# main.net
KiCad netlist of a schematic drawn in EAGLE
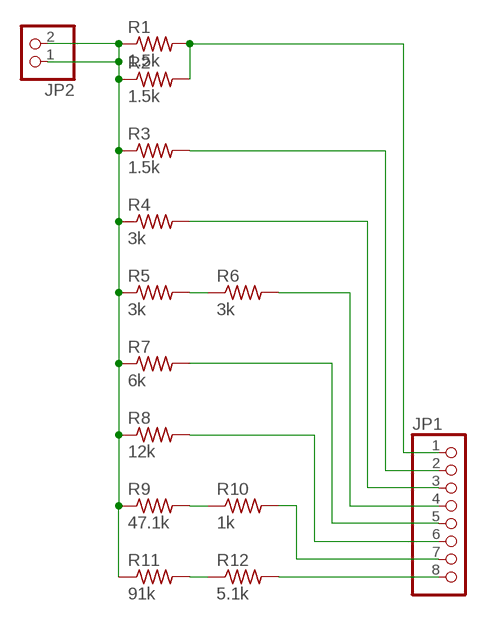
[diagram p0: schematic, sheet 1]

(export (version "E")
  (design (tool "Eeschema 10.0.6"))
  (components
    (comp (ref "JP1")
      (value "PINHD-1X8")
      (footprint "eagle-import:1X08")
      (libsource (lib "eagle-import") (part "PINHD-1X8"))
    )
    (comp (ref "JP2")
      (value "PINHD-1X2")
      (footprint "eagle-import:1X02")
      (libsource (lib "eagle-import") (part "PINHD-1X2"))
    )
    (comp (ref "R1")
      (value "1.5k")
      (footprint "eagle-import:0309_10")
      (libsource (lib "eagle-import") (part "R-US_0309/10"))
    )
    (comp (ref "R2")
      (value "1.5k")
      (footprint "eagle-import:0309_10")
      (libsource (lib "eagle-import") (part "R-US_0309/10"))
    )
    (comp (ref "R3")
      (value "1.5k")
      (footprint "eagle-import:0309_10")
      (libsource (lib "eagle-import") (part "R-US_0309/10"))
    )
    (comp (ref "R4")
      (value "3k")
      (footprint "eagle-import:0309_10")
      (libsource (lib "eagle-import") (part "R-US_0309/10"))
    )
    (comp (ref "R5")
      (value "3k")
      (footprint "eagle-import:0309_10")
      (libsource (lib "eagle-import") (part "R-US_0309/10"))
    )
    (comp (ref "R6")
      (value "3k")
      (footprint "eagle-import:0309_10")
      (libsource (lib "eagle-import") (part "R-US_0309/10"))
    )
    (comp (ref "R7")
      (value "6k")
      (footprint "eagle-import:0309_10")
      (libsource (lib "eagle-import") (part "R-US_0309/10"))
    )
    (comp (ref "R8")
      (value "12k")
      (footprint "eagle-import:0309_10")
      (libsource (lib "eagle-import") (part "R-US_0309/10"))
    )
    (comp (ref "R9")
      (value "47.1k")
      (footprint "eagle-import:0309_10")
      (libsource (lib "eagle-import") (part "R-US_0309/10"))
    )
    (comp (ref "R10")
      (value "1k")
      (footprint "eagle-import:0309_10")
      (libsource (lib "eagle-import") (part "R-US_0309/10"))
    )
    (comp (ref "R11")
      (value "91k")
      (footprint "eagle-import:0309_10")
      (libsource (lib "eagle-import") (part "R-US_0309/10"))
    )
    (comp (ref "R12")
      (value "5.1k")
      (footprint "eagle-import:0309_10")
      (libsource (lib "eagle-import") (part "R-US_0309/10"))
    )
  )
  (nets
    (net (code "1") (name "Net-(JP1-Pad1)") (class "Default")
      (node (ref "JP1") (pin "1") (pinfunction "1_1") (pintype "passive"))
      (node (ref "R1") (pin "2") (pinfunction "2_2") (pintype "passive"))
      (node (ref "R2") (pin "2") (pinfunction "2_2") (pintype "passive"))
    )
    (net (code "2") (name "Net-(JP1-Pad2)") (class "Default")
      (node (ref "JP1") (pin "2") (pinfunction "2_2") (pintype "passive"))
      (node (ref "R3") (pin "2") (pinfunction "2_2") (pintype "passive"))
    )
    (net (code "3") (name "Net-(JP1-Pad3)") (class "Default")
      (node (ref "JP1") (pin "3") (pinfunction "3_3") (pintype "passive"))
      (node (ref "R4") (pin "2") (pinfunction "2_2") (pintype "passive"))
    )
    (net (code "4") (name "Net-(JP1-Pad4)") (class "Default")
      (node (ref "JP1") (pin "4") (pinfunction "4_4") (pintype "passive"))
      (node (ref "R6") (pin "2") (pinfunction "2_2") (pintype "passive"))
    )
    (net (code "5") (name "Net-(JP1-Pad5)") (class "Default")
      (node (ref "JP1") (pin "5") (pinfunction "5_5") (pintype "passive"))
      (node (ref "R7") (pin "2") (pinfunction "2_2") (pintype "passive"))
    )
    (net (code "6") (name "Net-(JP1-Pad6)") (class "Default")
      (node (ref "JP1") (pin "6") (pinfunction "6_6") (pintype "passive"))
      (node (ref "R8") (pin "2") (pinfunction "2_2") (pintype "passive"))
    )
    (net (code "7") (name "Net-(JP1-Pad7)") (class "Default")
      (node (ref "JP1") (pin "7") (pinfunction "7_7") (pintype "passive"))
      (node (ref "R10") (pin "2") (pinfunction "2_2") (pintype "passive"))
    )
    (net (code "8") (name "Net-(JP1-Pad8)") (class "Default")
      (node (ref "JP1") (pin "8") (pinfunction "8_8") (pintype "passive"))
      (node (ref "R12") (pin "2") (pinfunction "2_2") (pintype "passive"))
    )
    (net (code "9") (name "Net-(JP2-Pad1)") (class "Default")
      (node (ref "JP2") (pin "1") (pinfunction "1_1") (pintype "passive"))
      (node (ref "JP2") (pin "2") (pinfunction "2_2") (pintype "passive"))
      (node (ref "R1") (pin "1") (pinfunction "1_1") (pintype "passive"))
      (node (ref "R11") (pin "1") (pinfunction "1_1") (pintype "passive"))
      (node (ref "R2") (pin "1") (pinfunction "1_1") (pintype "passive"))
      (node (ref "R3") (pin "1") (pinfunction "1_1") (pintype "passive"))
      (node (ref "R4") (pin "1") (pinfunction "1_1") (pintype "passive"))
      (node (ref "R5") (pin "1") (pinfunction "1_1") (pintype "passive"))
      (node (ref "R7") (pin "1") (pinfunction "1_1") (pintype "passive"))
      (node (ref "R8") (pin "1") (pinfunction "1_1") (pintype "passive"))
      (node (ref "R9") (pin "1") (pinfunction "1_1") (pintype "passive"))
    )
    (net (code "10") (name "Net-(R5-Pad2)") (class "Default")
      (node (ref "R5") (pin "2") (pinfunction "2_2") (pintype "passive"))
      (node (ref "R6") (pin "1") (pinfunction "1_1") (pintype "passive"))
    )
    (net (code "11") (name "Net-(R10-Pad1)") (class "Default")
      (node (ref "R10") (pin "1") (pinfunction "1_1") (pintype "passive"))
      (node (ref "R9") (pin "2") (pinfunction "2_2") (pintype "passive"))
    )
    (net (code "12") (name "Net-(R11-Pad2)") (class "Default")
      (node (ref "R11") (pin "2") (pinfunction "2_2") (pintype "passive"))
      (node (ref "R12") (pin "1") (pinfunction "1_1") (pintype "passive"))
    )
  )
)
